# Reflow_Ch_teau.net
KiCad netlist of a schematic drawn in EAGLE
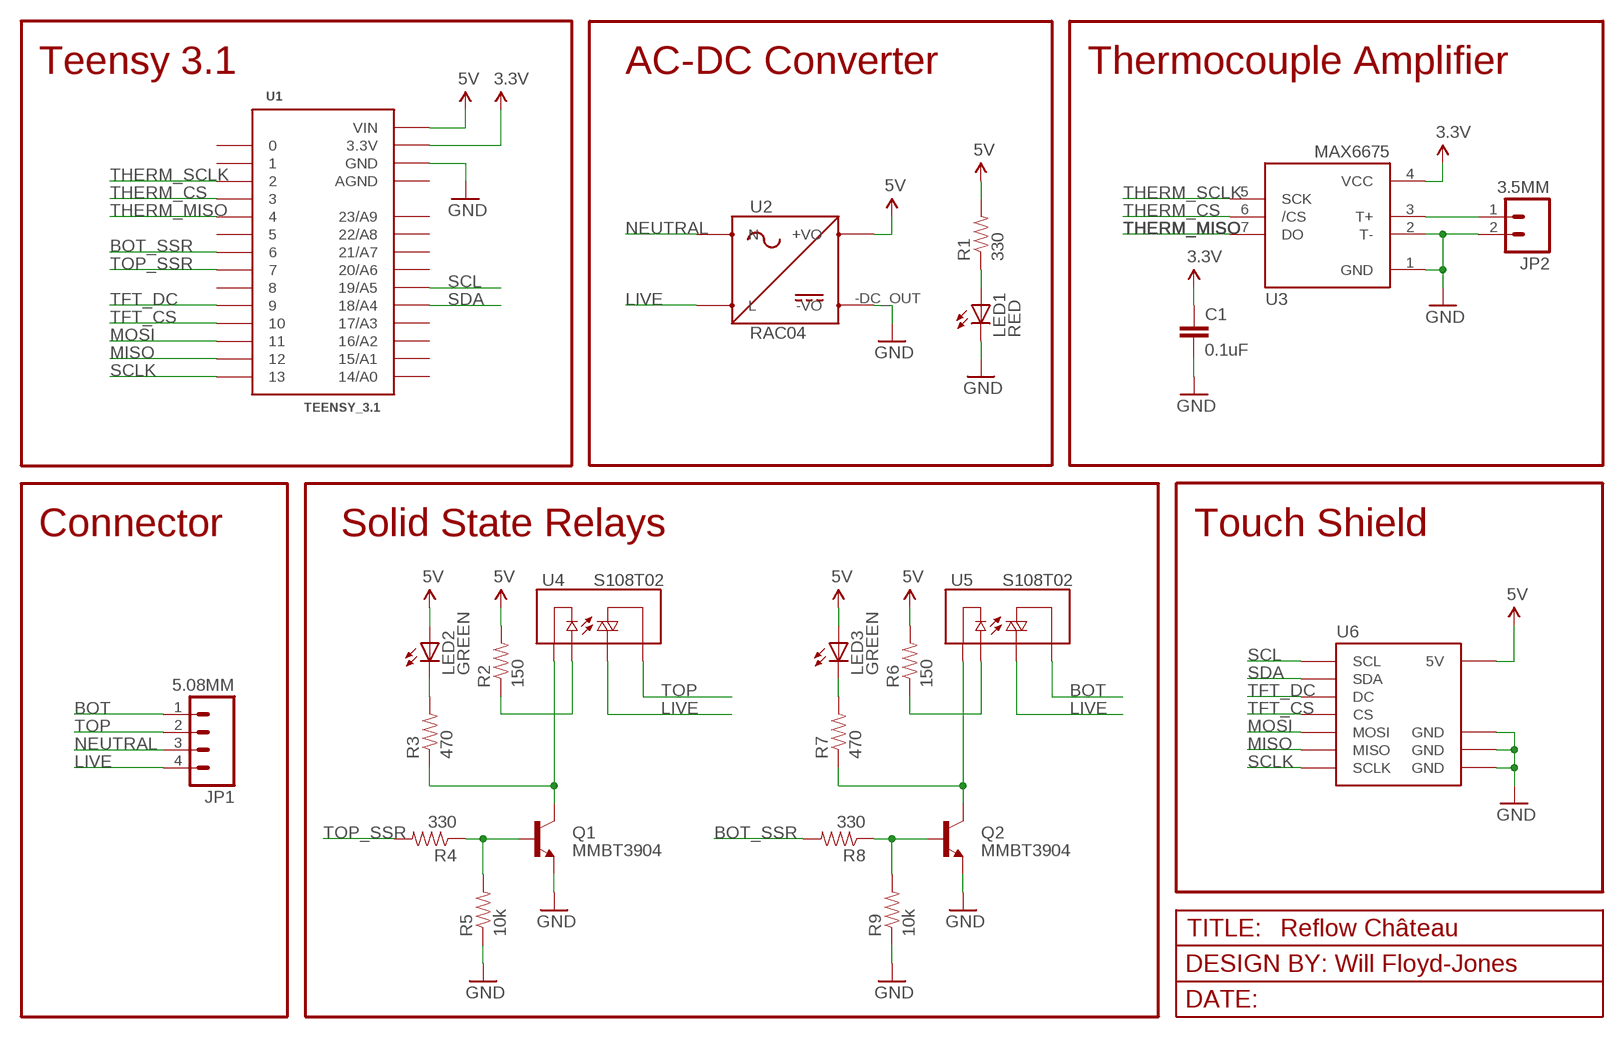
[diagram p0: schematic, sheet 1]

(export (version "E")
  (design (tool "Eeschema 10.0.6"))
  (components
    (comp (ref "C1")
      (value "0.1uF")
      (footprint "eagle-import:0603-CAP")
      (libsource (lib "eagle-import") (part "CAP0603-CAP"))
    )
    (comp (ref "JP1")
      (value "5.08MM")
      (footprint "eagle-import:SCREWTERMINAL-5.08MM-4")
      (libsource (lib "eagle-import") (part "SCREWTERMINAL-5.08MM-4"))
    )
    (comp (ref "JP2")
      (value "3.5MM")
      (footprint "eagle-import:SCREWTERMINAL-3.5MM-2_LOCK")
      (libsource (lib "eagle-import") (part "SCREWTERMINAL-3.5MM-2_LOCK"))
    )
    (comp (ref "LED1")
      (value "RED")
      (footprint "eagle-import:LED-1206")
      (libsource (lib "eagle-import") (part "LED-RED1206"))
    )
    (comp (ref "LED2")
      (value "GREEN")
      (footprint "eagle-import:LED-1206")
      (libsource (lib "eagle-import") (part "LED-GREENLILYPAD"))
    )
    (comp (ref "LED3")
      (value "GREEN")
      (footprint "eagle-import:LED-1206")
      (libsource (lib "eagle-import") (part "LED-GREENLILYPAD"))
    )
    (comp (ref "Q1")
      (value "MMBT3904")
      (footprint "eagle-import:SOT23-3")
      (libsource (lib "eagle-import") (part "TRANSISTOR_NPNMMBT2222A"))
    )
    (comp (ref "Q2")
      (value "MMBT3904")
      (footprint "eagle-import:SOT23-3")
      (libsource (lib "eagle-import") (part "TRANSISTOR_NPNMMBT2222A"))
    )
    (comp (ref "R1")
      (value "330")
      (footprint "eagle-import:0603-RES")
      (libsource (lib "eagle-import") (part "RESISTOR0603-RES"))
    )
    (comp (ref "R2")
      (value "150")
      (footprint "eagle-import:0603-RES")
      (libsource (lib "eagle-import") (part "RESISTOR0603"))
    )
    (comp (ref "R3")
      (value "470")
      (footprint "eagle-import:0603-RES")
      (libsource (lib "eagle-import") (part "RESISTOR0603"))
    )
    (comp (ref "R4")
      (value "330")
      (footprint "eagle-import:0603-RES")
      (libsource (lib "eagle-import") (part "RESISTOR0603"))
    )
    (comp (ref "R5")
      (value "10k")
      (footprint "eagle-import:0603-RES")
      (libsource (lib "eagle-import") (part "RESISTOR0603"))
    )
    (comp (ref "R6")
      (value "150")
      (footprint "eagle-import:0603-RES")
      (libsource (lib "eagle-import") (part "RESISTOR0603"))
    )
    (comp (ref "R7")
      (value "470")
      (footprint "eagle-import:0603-RES")
      (libsource (lib "eagle-import") (part "RESISTOR0603"))
    )
    (comp (ref "R8")
      (value "330")
      (footprint "eagle-import:0603-RES")
      (libsource (lib "eagle-import") (part "RESISTOR0603"))
    )
    (comp (ref "R9")
      (value "10k")
      (footprint "eagle-import:0603-RES")
      (libsource (lib "eagle-import") (part "RESISTOR0603"))
    )
    (comp (ref "U$9")
      (value "FRAME")
      (footprint "eagle-import:F-J_LOGO")
      (libsource (lib "eagle-import") (part "FRAME"))
    )
    (comp (ref "U1")
      (value "TEENSY_3.1")
      (footprint "eagle-import:TEENSY_3.1")
      (libsource (lib "eagle-import") (part "TEENSY_3.1"))
    )
    (comp (ref "U2")
      (value "RAC04")
      (footprint "eagle-import:RAC04")
      (libsource (lib "eagle-import") (part "RAC04"))
    )
    (comp (ref "U3")
      (value "MAX6675")
      (footprint "eagle-import:SO08")
      (libsource (lib "eagle-import") (part "MAX6675"))
    )
    (comp (ref "U4")
      (value "S108T02")
      (footprint "eagle-import:RELAY-S108T02")
      (libsource (lib "eagle-import") (part "RELAY-SOLIDSTATEPTH"))
    )
    (comp (ref "U5")
      (value "S108T02")
      (footprint "eagle-import:RELAY-S108T02")
      (libsource (lib "eagle-import") (part "RELAY-SOLIDSTATEPTH"))
    )
    (comp (ref "U6")
      (value "CAPACITIVE_TOUCH")
      (footprint "eagle-import:CAPACITIVE_TOUCH")
      (libsource (lib "eagle-import") (part "CAPACITIVE_TOUCH"))
    )
  )
  (nets
    (net (code "1") (name "/AGND") (class "Default")
      (node (ref "U1") (pin "AGND") (pinfunction "AGND_AGND") (pintype "power_in"))
    )
    (net (code "2") (name "/BOT") (class "Default")
      (node (ref "JP1") (pin "1") (pinfunction "1_1") (pintype "passive"))
      (node (ref "U5") (pin "1") (pinfunction "T1_1") (pintype "bidirectional"))
    )
    (net (code "3") (name "/BOT_SSR") (class "Default")
      (node (ref "R8") (pin "2") (pinfunction "2_2") (pintype "passive"))
      (node (ref "U1") (pin "6") (pinfunction "6_6") (pintype "bidirectional"))
    )
    (net (code "4") (name "/LIVE") (class "Default")
      (node (ref "JP1") (pin "4") (pinfunction "4_4") (pintype "passive"))
      (node (ref "U2") (pin "LIVE") (pinfunction "L_LIVE") (pintype "bidirectional"))
      (node (ref "U4") (pin "2") (pinfunction "T2_2") (pintype "bidirectional"))
      (node (ref "U5") (pin "2") (pinfunction "T2_2") (pintype "bidirectional"))
    )
    (net (code "5") (name "/MISO") (class "Default")
      (node (ref "U1") (pin "12") (pinfunction "12_12") (pintype "bidirectional"))
      (node (ref "U6") (pin "D12") (pinfunction "MISO_D12") (pintype "bidirectional"))
    )
    (net (code "6") (name "/MOSI") (class "Default")
      (node (ref "U1") (pin "11") (pinfunction "11_11") (pintype "bidirectional"))
      (node (ref "U6") (pin "D11") (pinfunction "MOSI_D11") (pintype "bidirectional"))
    )
    (net (code "7") (name "/NEUTRAL") (class "Default")
      (node (ref "JP1") (pin "3") (pinfunction "3_3") (pintype "passive"))
      (node (ref "U2") (pin "NEUTRAL") (pinfunction "N_NEUTRAL") (pintype "bidirectional"))
    )
    (net (code "8") (name "/SCL") (class "Default")
      (node (ref "U1") (pin "19/A5") (pinfunction "19/A5_19/A5") (pintype "bidirectional"))
      (node (ref "U6") (pin "SCL") (pinfunction "SCL_SCL") (pintype "bidirectional"))
    )
    (net (code "9") (name "/SCLK") (class "Default")
      (node (ref "U1") (pin "13") (pinfunction "13_13") (pintype "bidirectional"))
      (node (ref "U6") (pin "D13") (pinfunction "SCLK_D13") (pintype "bidirectional"))
    )
    (net (code "10") (name "/SDA") (class "Default")
      (node (ref "U1") (pin "18/A4") (pinfunction "18/A4_18/A4") (pintype "bidirectional"))
      (node (ref "U6") (pin "SDA") (pinfunction "SDA_SDA") (pintype "bidirectional"))
    )
    (net (code "11") (name "/TFT_CS") (class "Default")
      (node (ref "U1") (pin "10") (pinfunction "10_10") (pintype "bidirectional"))
      (node (ref "U6") (pin "D10") (pinfunction "CS_D10") (pintype "bidirectional"))
    )
    (net (code "12") (name "/TFT_DC") (class "Default")
      (node (ref "U1") (pin "9") (pinfunction "9_9") (pintype "bidirectional"))
      (node (ref "U6") (pin "D9") (pinfunction "DC_D9") (pintype "bidirectional"))
    )
    (net (code "13") (name "/THERM_CS") (class "Default")
      (node (ref "U1") (pin "3") (pinfunction "3_3") (pintype "bidirectional"))
      (node (ref "U3") (pin "6") (pinfunction "/CS_6") (pintype "input"))
    )
    (net (code "14") (name "/THERM_MISO") (class "Default")
      (node (ref "U1") (pin "4") (pinfunction "4_4") (pintype "bidirectional"))
      (node (ref "U3") (pin "7") (pinfunction "DO_7") (pintype "output"))
    )
    (net (code "15") (name "/THERM_SCLK") (class "Default")
      (node (ref "U1") (pin "2") (pinfunction "2_2") (pintype "bidirectional"))
      (node (ref "U3") (pin "5") (pinfunction "SCK_5") (pintype "input"))
    )
    (net (code "16") (name "/TOP") (class "Default")
      (node (ref "JP1") (pin "2") (pinfunction "2_2") (pintype "passive"))
      (node (ref "U4") (pin "1") (pinfunction "T1_1") (pintype "bidirectional"))
    )
    (net (code "17") (name "/TOP_SSR") (class "Default")
      (node (ref "R4") (pin "2") (pinfunction "2_2") (pintype "passive"))
      (node (ref "U1") (pin "7") (pinfunction "7_7") (pintype "bidirectional"))
    )
    (net (code "18") (name "3.3V") (class "Default")
      (node (ref "C1") (pin "1") (pinfunction "1_1") (pintype "passive"))
      (node (ref "U1") (pin "3.3V") (pinfunction "3.3V_3.3V") (pintype "power_in"))
      (node (ref "U3") (pin "4") (pinfunction "VCC_4") (pintype "power_in"))
    )
    (net (code "19") (name "5V") (class "Default")
      (node (ref "LED2") (pin "A") (pinfunction "A_A") (pintype "passive"))
      (node (ref "LED3") (pin "A") (pinfunction "A_A") (pintype "passive"))
      (node (ref "R1") (pin "2") (pinfunction "2_2") (pintype "passive"))
      (node (ref "R2") (pin "2") (pinfunction "2_2") (pintype "passive"))
      (node (ref "R6") (pin "2") (pinfunction "2_2") (pintype "passive"))
      (node (ref "U1") (pin "VIN") (pinfunction "VIN_VIN") (pintype "power_in"))
      (node (ref "U2") (pin "+DC_OUT") (pinfunction "+VO_+DC_OUT") (pintype "bidirectional"))
      (node (ref "U6") (pin "5V") (pinfunction "5V_5V") (pintype "bidirectional"))
    )
    (net (code "20") (name "GND") (class "Default")
      (node (ref "C1") (pin "2") (pinfunction "2_2") (pintype "passive"))
      (node (ref "JP2") (pin "2") (pinfunction "2_2") (pintype "passive"))
      (node (ref "LED1") (pin "C") (pinfunction "C_C") (pintype "passive"))
      (node (ref "Q1") (pin "2") (pinfunction "E_2") (pintype "passive"))
      (node (ref "Q2") (pin "2") (pinfunction "E_2") (pintype "passive"))
      (node (ref "R5") (pin "1") (pinfunction "1_1") (pintype "passive"))
      (node (ref "R9") (pin "1") (pinfunction "1_1") (pintype "passive"))
      (node (ref "U1") (pin "GND") (pinfunction "GND_GND") (pintype "power_in"))
      (node (ref "U2") (pin "-DC_OUT") (pinfunction "-VO_-DC_OUT") (pintype "bidirectional"))
      (node (ref "U3") (pin "1") (pinfunction "GND_1") (pintype "power_in"))
      (node (ref "U3") (pin "2") (pinfunction "T-_2") (pintype "input"))
      (node (ref "U6") (pin "GND") (pinfunction "GND_GND") (pintype "bidirectional"))
      (node (ref "U6") (pin "GND@1") (pinfunction "GND_GND@1") (pintype "bidirectional"))
      (node (ref "U6") (pin "GND@2") (pinfunction "GND_GND@2") (pintype "bidirectional"))
    )
    (net (code "21") (name "Net-(LED1-PadA)") (class "Default")
      (node (ref "LED1") (pin "A") (pinfunction "A_A") (pintype "passive"))
      (node (ref "R1") (pin "1") (pinfunction "1_1") (pintype "passive"))
    )
    (net (code "22") (name "Net-(LED2-PadC)") (class "Default")
      (node (ref "LED2") (pin "C") (pinfunction "C_C") (pintype "passive"))
      (node (ref "R3") (pin "2") (pinfunction "2_2") (pintype "passive"))
    )
    (net (code "23") (name "Net-(LED3-PadC)") (class "Default")
      (node (ref "LED3") (pin "C") (pinfunction "C_C") (pintype "passive"))
      (node (ref "R7") (pin "2") (pinfunction "2_2") (pintype "passive"))
    )
    (net (code "24") (name "Net-(Q1-B)") (class "Default")
      (node (ref "Q1") (pin "1") (pinfunction "B_1") (pintype "passive"))
      (node (ref "R4") (pin "1") (pinfunction "1_1") (pintype "passive"))
      (node (ref "R5") (pin "2") (pinfunction "2_2") (pintype "passive"))
    )
    (net (code "25") (name "Net-(Q1-C)") (class "Default")
      (node (ref "Q1") (pin "3") (pinfunction "C_3") (pintype "passive"))
      (node (ref "R3") (pin "1") (pinfunction "1_1") (pintype "passive"))
      (node (ref "U4") (pin "4") (pinfunction "-_4") (pintype "bidirectional"))
    )
    (net (code "26") (name "Net-(Q2-B)") (class "Default")
      (node (ref "Q2") (pin "1") (pinfunction "B_1") (pintype "passive"))
      (node (ref "R8") (pin "1") (pinfunction "1_1") (pintype "passive"))
      (node (ref "R9") (pin "2") (pinfunction "2_2") (pintype "passive"))
    )
    (net (code "27") (name "Net-(Q2-C)") (class "Default")
      (node (ref "Q2") (pin "3") (pinfunction "C_3") (pintype "passive"))
      (node (ref "R7") (pin "1") (pinfunction "1_1") (pintype "passive"))
      (node (ref "U5") (pin "4") (pinfunction "-_4") (pintype "bidirectional"))
    )
    (net (code "28") (name "Net-(U3-T+)") (class "Default")
      (node (ref "JP2") (pin "1") (pinfunction "1_1") (pintype "passive"))
      (node (ref "U3") (pin "3") (pinfunction "T+_3") (pintype "input"))
    )
    (net (code "29") (name "Net-(U4-+)") (class "Default")
      (node (ref "R2") (pin "1") (pinfunction "1_1") (pintype "passive"))
      (node (ref "U4") (pin "3") (pinfunction "+_3") (pintype "bidirectional"))
    )
    (net (code "30") (name "Net-(U5-+)") (class "Default")
      (node (ref "R6") (pin "1") (pinfunction "1_1") (pintype "passive"))
      (node (ref "U5") (pin "3") (pinfunction "+_3") (pintype "bidirectional"))
    )
    (net (code "31") (name "unconnected-(U1-Pad0)") (class "Default")
      (node (ref "U1") (pin "0") (pinfunction "0_0") (pintype "bidirectional"))
    )
    (net (code "32") (name "unconnected-(U1-Pad1)") (class "Default")
      (node (ref "U1") (pin "1") (pinfunction "1_1") (pintype "bidirectional"))
    )
    (net (code "33") (name "unconnected-(U1-Pad5)") (class "Default")
      (node (ref "U1") (pin "5") (pinfunction "5_5") (pintype "bidirectional"))
    )
    (net (code "34") (name "unconnected-(U1-Pad8)") (class "Default")
      (node (ref "U1") (pin "8") (pinfunction "8_8") (pintype "bidirectional"))
    )
    (net (code "35") (name "unconnected-(U1-Pad14{slash}A0)") (class "Default")
      (node (ref "U1") (pin "14/A0") (pinfunction "14/A0_14/A0") (pintype "bidirectional"))
    )
    (net (code "36") (name "unconnected-(U1-Pad15{slash}A1)") (class "Default")
      (node (ref "U1") (pin "15/A1") (pinfunction "15/A1_15/A1") (pintype "bidirectional"))
    )
    (net (code "37") (name "unconnected-(U1-Pad16{slash}A2)") (class "Default")
      (node (ref "U1") (pin "16/A2") (pinfunction "16/A2_16/A2") (pintype "bidirectional"))
    )
    (net (code "38") (name "unconnected-(U1-Pad17{slash}A3)") (class "Default")
      (node (ref "U1") (pin "17/A3") (pinfunction "17/A3_17/A3") (pintype "bidirectional"))
    )
    (net (code "39") (name "unconnected-(U1-Pad20{slash}A6)") (class "Default")
      (node (ref "U1") (pin "20/A6") (pinfunction "20/A6_20/A6") (pintype "bidirectional"))
    )
    (net (code "40") (name "unconnected-(U1-Pad21{slash}A7)") (class "Default")
      (node (ref "U1") (pin "21/A7") (pinfunction "21/A7_21/A7") (pintype "bidirectional"))
    )
    (net (code "41") (name "unconnected-(U1-Pad22{slash}A8)") (class "Default")
      (node (ref "U1") (pin "22/A8") (pinfunction "22/A8_22/A8") (pintype "bidirectional"))
    )
    (net (code "42") (name "unconnected-(U1-Pad23{slash}A9)") (class "Default")
      (node (ref "U1") (pin "23/A9") (pinfunction "23/A9_23/A9") (pintype "bidirectional"))
    )
  )
)
